# can_rgx_led.net
KiCad netlist of a schematic drawn in EAGLE
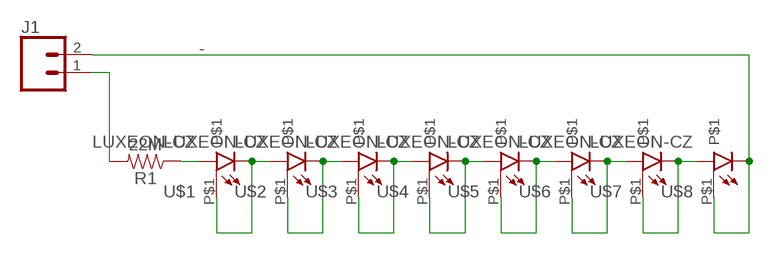
[diagram p0: schematic, sheet 1]

(export (version "E")
  (design (tool "Eeschema 10.0.6"))
  (components
    (comp (ref "J1")
      (value "CONN_02")
      (footprint "eagle-import:1X02")
      (libsource (lib "eagle-import") (part "CONN_02"))
    )
    (comp (ref "R1")
      (value "22M")
      (footprint "eagle-import:0603")
      (libsource (lib "eagle-import") (part "22MOHM-0603-1/10W-10%"))
    )
    (comp (ref "U$1")
      (value "LUXEON-CZ")
      (footprint "eagle-import:LUXEON-CZ")
      (libsource (lib "eagle-import") (part "LUXEON-CZ"))
    )
    (comp (ref "U$2")
      (value "LUXEON-CZ")
      (footprint "eagle-import:LUXEON-CZ")
      (libsource (lib "eagle-import") (part "LUXEON-CZ"))
    )
    (comp (ref "U$3")
      (value "LUXEON-CZ")
      (footprint "eagle-import:LUXEON-CZ")
      (libsource (lib "eagle-import") (part "LUXEON-CZ"))
    )
    (comp (ref "U$4")
      (value "LUXEON-CZ")
      (footprint "eagle-import:LUXEON-CZ")
      (libsource (lib "eagle-import") (part "LUXEON-CZ"))
    )
    (comp (ref "U$5")
      (value "LUXEON-CZ")
      (footprint "eagle-import:LUXEON-CZ")
      (libsource (lib "eagle-import") (part "LUXEON-CZ"))
    )
    (comp (ref "U$6")
      (value "LUXEON-CZ")
      (footprint "eagle-import:LUXEON-CZ")
      (libsource (lib "eagle-import") (part "LUXEON-CZ"))
    )
    (comp (ref "U$7")
      (value "LUXEON-CZ")
      (footprint "eagle-import:LUXEON-CZ")
      (libsource (lib "eagle-import") (part "LUXEON-CZ"))
    )
    (comp (ref "U$8")
      (value "LUXEON-CZ")
      (footprint "eagle-import:LUXEON-CZ")
      (libsource (lib "eagle-import") (part "LUXEON-CZ"))
    )
  )
  (nets
    (net (code "1") (name "/-") (class "Default")
      (node (ref "J1") (pin "2") (pinfunction "2_2") (pintype "passive"))
      (node (ref "U$8") (pin "P$1") (pinfunction "P$1_P$1") (pintype "bidirectional"))
      (node (ref "U$8") (pin "P$3") (pinfunction "C_P$3") (pintype "passive"))
    )
    (net (code "2") (name "Net-(J1-Pad1)") (class "Default")
      (node (ref "J1") (pin "1") (pinfunction "1_1") (pintype "passive"))
      (node (ref "R1") (pin "2") (pinfunction "2_2") (pintype "passive"))
    )
    (net (code "3") (name "Net-(U$1-A)") (class "Default")
      (node (ref "R1") (pin "1") (pinfunction "1_1") (pintype "passive"))
      (node (ref "U$1") (pin "P$2") (pinfunction "A_P$2") (pintype "passive"))
    )
    (net (code "4") (name "Net-(U$1-C)") (class "Default")
      (node (ref "U$1") (pin "P$1") (pinfunction "P$1_P$1") (pintype "bidirectional"))
      (node (ref "U$1") (pin "P$3") (pinfunction "C_P$3") (pintype "passive"))
      (node (ref "U$2") (pin "P$2") (pinfunction "A_P$2") (pintype "passive"))
    )
    (net (code "5") (name "Net-(U$2-C)") (class "Default")
      (node (ref "U$2") (pin "P$1") (pinfunction "P$1_P$1") (pintype "bidirectional"))
      (node (ref "U$2") (pin "P$3") (pinfunction "C_P$3") (pintype "passive"))
      (node (ref "U$3") (pin "P$2") (pinfunction "A_P$2") (pintype "passive"))
    )
    (net (code "6") (name "Net-(U$3-C)") (class "Default")
      (node (ref "U$3") (pin "P$1") (pinfunction "P$1_P$1") (pintype "bidirectional"))
      (node (ref "U$3") (pin "P$3") (pinfunction "C_P$3") (pintype "passive"))
      (node (ref "U$4") (pin "P$2") (pinfunction "A_P$2") (pintype "passive"))
    )
    (net (code "7") (name "Net-(U$4-C)") (class "Default")
      (node (ref "U$4") (pin "P$1") (pinfunction "P$1_P$1") (pintype "bidirectional"))
      (node (ref "U$4") (pin "P$3") (pinfunction "C_P$3") (pintype "passive"))
      (node (ref "U$5") (pin "P$2") (pinfunction "A_P$2") (pintype "passive"))
    )
    (net (code "8") (name "Net-(U$5-C)") (class "Default")
      (node (ref "U$5") (pin "P$1") (pinfunction "P$1_P$1") (pintype "bidirectional"))
      (node (ref "U$5") (pin "P$3") (pinfunction "C_P$3") (pintype "passive"))
      (node (ref "U$6") (pin "P$2") (pinfunction "A_P$2") (pintype "passive"))
    )
    (net (code "9") (name "Net-(U$6-C)") (class "Default")
      (node (ref "U$6") (pin "P$1") (pinfunction "P$1_P$1") (pintype "bidirectional"))
      (node (ref "U$6") (pin "P$3") (pinfunction "C_P$3") (pintype "passive"))
      (node (ref "U$7") (pin "P$2") (pinfunction "A_P$2") (pintype "passive"))
    )
    (net (code "10") (name "Net-(U$7-C)") (class "Default")
      (node (ref "U$7") (pin "P$1") (pinfunction "P$1_P$1") (pintype "bidirectional"))
      (node (ref "U$7") (pin "P$3") (pinfunction "C_P$3") (pintype "passive"))
      (node (ref "U$8") (pin "P$2") (pinfunction "A_P$2") (pintype "passive"))
    )
  )
)
